# IN-17_tubes_V1_1.net
KiCad netlist of a schematic drawn in EAGLE
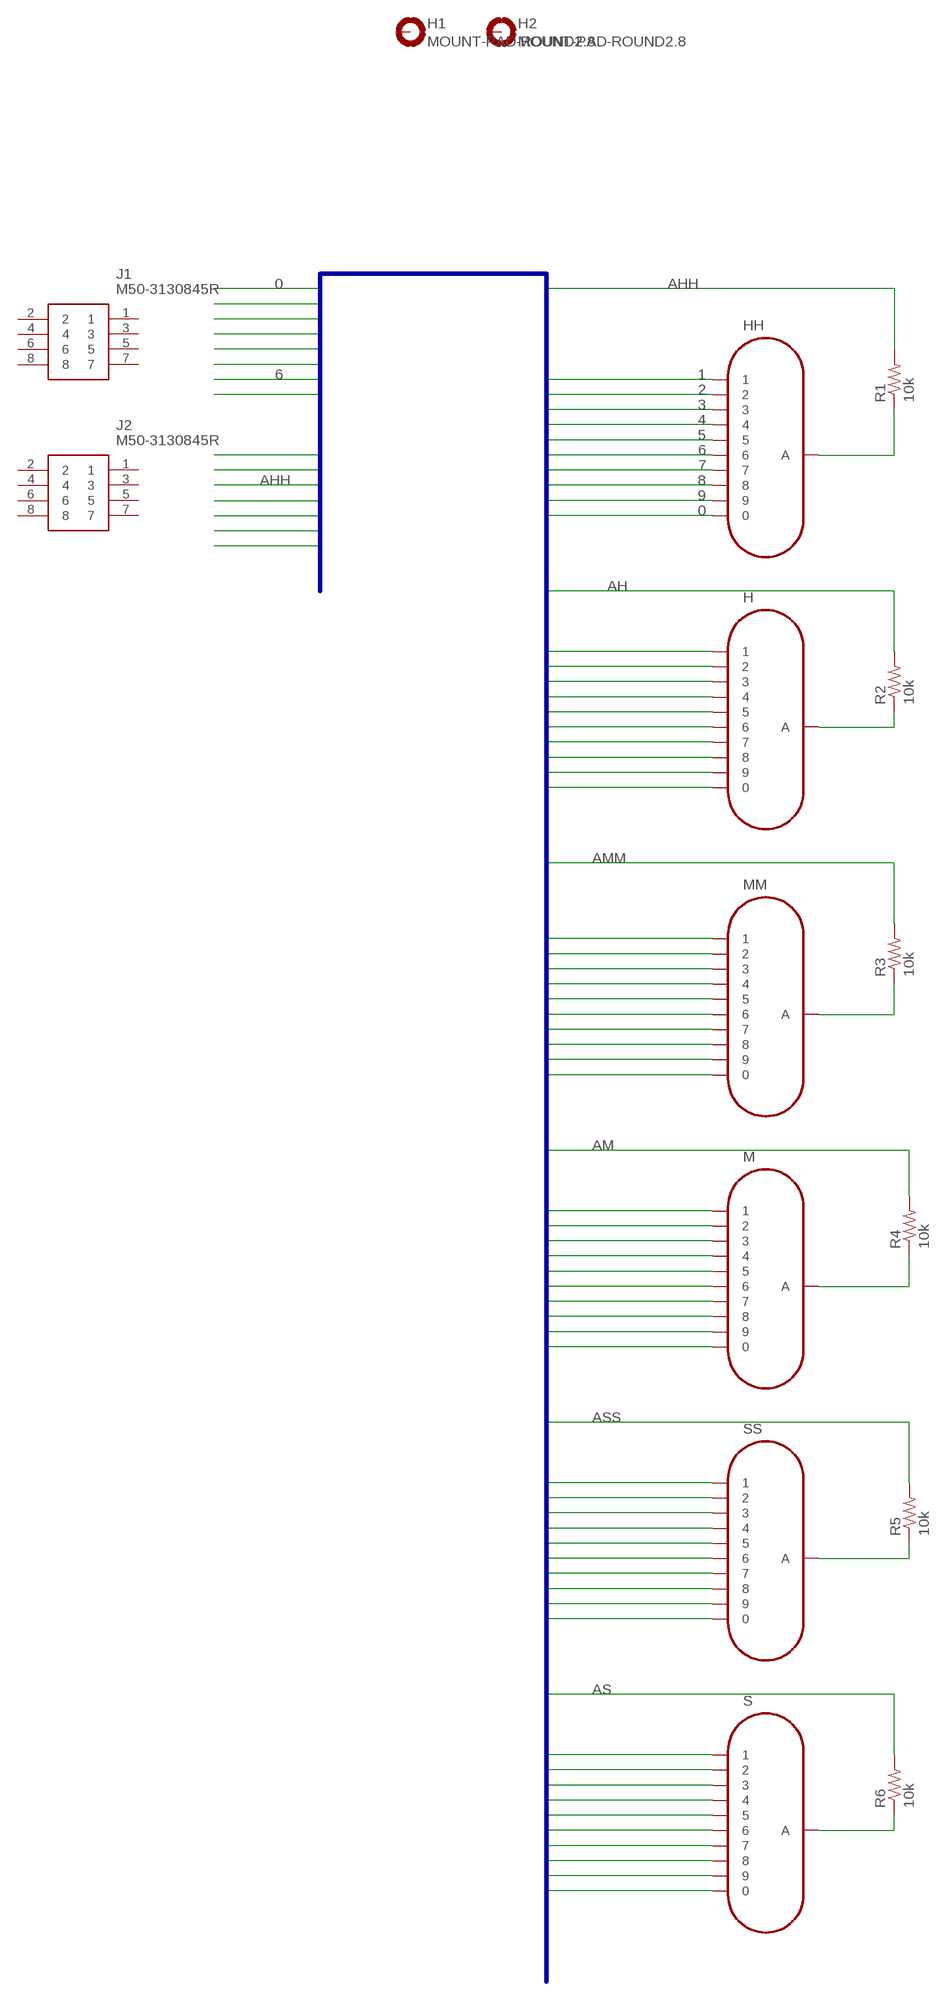
[diagram p0: schematic, sheet 1]

(export (version "E")
  (design (tool "Eeschema 10.0.6"))
  (components
    (comp (ref "H")
      (value "IN-17")
      (footprint "eagle-import:IN-17")
      (libsource (lib "eagle-import") (part "IN-17"))
    )
    (comp (ref "H1")
      (value "MOUNT-PAD-ROUND2.8")
      (footprint "eagle-import:2,8-PAD")
      (libsource (lib "eagle-import") (part "MOUNT-PAD-ROUND2.8"))
    )
    (comp (ref "H2")
      (value "MOUNT-PAD-ROUND2.8")
      (footprint "eagle-import:2,8-PAD")
      (libsource (lib "eagle-import") (part "MOUNT-PAD-ROUND2.8"))
    )
    (comp (ref "HH")
      (value "IN-17")
      (footprint "eagle-import:IN-17")
      (libsource (lib "eagle-import") (part "IN-17"))
    )
    (comp (ref "J1")
      (value "M50-3130845R")
      (footprint "eagle-import:M503130845R")
      (fields (field (name "MOUSER_PART_NUMBER") "855-M50-3130845R"))
      (libsource (lib "eagle-import") (part "M50-3130845R"))
    )
    (comp (ref "J2")
      (value "M50-3130845R")
      (footprint "eagle-import:M503130845R")
      (fields (field (name "MOUSER_PART_NUMBER") "855-M50-3130845R"))
      (libsource (lib "eagle-import") (part "M50-3130845R"))
    )
    (comp (ref "M")
      (value "IN-17")
      (footprint "eagle-import:IN-17")
      (libsource (lib "eagle-import") (part "IN-17"))
    )
    (comp (ref "MM")
      (value "IN-17")
      (footprint "eagle-import:IN-17")
      (libsource (lib "eagle-import") (part "IN-17"))
    )
    (comp (ref "R1")
      (value "10k")
      (footprint "eagle-import:R0805")
      (libsource (lib "eagle-import") (part "R-US_R0805"))
    )
    (comp (ref "R2")
      (value "10k")
      (footprint "eagle-import:R0805")
      (libsource (lib "eagle-import") (part "R-US_R0805"))
    )
    (comp (ref "R3")
      (value "10k")
      (footprint "eagle-import:R0805")
      (libsource (lib "eagle-import") (part "R-US_R0805"))
    )
    (comp (ref "R4")
      (value "10k")
      (footprint "eagle-import:R0805")
      (libsource (lib "eagle-import") (part "R-US_R0805"))
    )
    (comp (ref "R5")
      (value "10k")
      (footprint "eagle-import:R0805")
      (libsource (lib "eagle-import") (part "R-US_R0805"))
    )
    (comp (ref "R6")
      (value "10k")
      (footprint "eagle-import:R0805")
      (libsource (lib "eagle-import") (part "R-US_R0805"))
    )
    (comp (ref "S")
      (value "IN-17")
      (footprint "eagle-import:IN-17")
      (libsource (lib "eagle-import") (part "IN-17"))
    )
    (comp (ref "SS")
      (value "IN-17")
      (footprint "eagle-import:IN-17")
      (libsource (lib "eagle-import") (part "IN-17"))
    )
  )
  (nets
    (net (code "1") (name "/0") (class "Default")
      (node (ref "H") (pin "0") (pinfunction "0_0") (pintype "bidirectional"))
      (node (ref "HH") (pin "0") (pinfunction "0_0") (pintype "bidirectional"))
      (node (ref "M") (pin "0") (pinfunction "0_0") (pintype "bidirectional"))
      (node (ref "MM") (pin "0") (pinfunction "0_0") (pintype "bidirectional"))
      (node (ref "S") (pin "0") (pinfunction "0_0") (pintype "bidirectional"))
      (node (ref "SS") (pin "0") (pinfunction "0_0") (pintype "bidirectional"))
    )
    (net (code "2") (name "/1") (class "Default")
      (node (ref "H") (pin "1") (pinfunction "1_1") (pintype "bidirectional"))
      (node (ref "HH") (pin "1") (pinfunction "1_1") (pintype "bidirectional"))
      (node (ref "M") (pin "1") (pinfunction "1_1") (pintype "bidirectional"))
      (node (ref "MM") (pin "1") (pinfunction "1_1") (pintype "bidirectional"))
      (node (ref "S") (pin "1") (pinfunction "1_1") (pintype "bidirectional"))
      (node (ref "SS") (pin "1") (pinfunction "1_1") (pintype "bidirectional"))
    )
    (net (code "3") (name "/2") (class "Default")
      (node (ref "H") (pin "2") (pinfunction "2_2") (pintype "bidirectional"))
      (node (ref "HH") (pin "2") (pinfunction "2_2") (pintype "bidirectional"))
      (node (ref "M") (pin "2") (pinfunction "2_2") (pintype "bidirectional"))
      (node (ref "MM") (pin "2") (pinfunction "2_2") (pintype "bidirectional"))
      (node (ref "S") (pin "2") (pinfunction "2_2") (pintype "bidirectional"))
      (node (ref "SS") (pin "2") (pinfunction "2_2") (pintype "bidirectional"))
    )
    (net (code "4") (name "/3") (class "Default")
      (node (ref "H") (pin "3") (pinfunction "3_3") (pintype "bidirectional"))
      (node (ref "HH") (pin "3") (pinfunction "3_3") (pintype "bidirectional"))
      (node (ref "M") (pin "3") (pinfunction "3_3") (pintype "bidirectional"))
      (node (ref "MM") (pin "3") (pinfunction "3_3") (pintype "bidirectional"))
      (node (ref "S") (pin "3") (pinfunction "3_3") (pintype "bidirectional"))
      (node (ref "SS") (pin "3") (pinfunction "3_3") (pintype "bidirectional"))
    )
    (net (code "5") (name "/4") (class "Default")
      (node (ref "H") (pin "4") (pinfunction "4_4") (pintype "bidirectional"))
      (node (ref "HH") (pin "4") (pinfunction "4_4") (pintype "bidirectional"))
      (node (ref "M") (pin "4") (pinfunction "4_4") (pintype "bidirectional"))
      (node (ref "MM") (pin "4") (pinfunction "4_4") (pintype "bidirectional"))
      (node (ref "S") (pin "4") (pinfunction "4_4") (pintype "bidirectional"))
      (node (ref "SS") (pin "4") (pinfunction "4_4") (pintype "bidirectional"))
    )
    (net (code "6") (name "/5") (class "Default")
      (node (ref "H") (pin "5") (pinfunction "5_5") (pintype "bidirectional"))
      (node (ref "HH") (pin "5") (pinfunction "5_5") (pintype "bidirectional"))
      (node (ref "M") (pin "5") (pinfunction "5_5") (pintype "bidirectional"))
      (node (ref "MM") (pin "5") (pinfunction "5_5") (pintype "bidirectional"))
      (node (ref "S") (pin "5") (pinfunction "5_5") (pintype "bidirectional"))
      (node (ref "SS") (pin "5") (pinfunction "5_5") (pintype "bidirectional"))
    )
    (net (code "7") (name "/6") (class "Default")
      (node (ref "H") (pin "6") (pinfunction "6_6") (pintype "bidirectional"))
      (node (ref "HH") (pin "6") (pinfunction "6_6") (pintype "bidirectional"))
      (node (ref "M") (pin "6") (pinfunction "6_6") (pintype "bidirectional"))
      (node (ref "MM") (pin "6") (pinfunction "6_6") (pintype "bidirectional"))
      (node (ref "S") (pin "6") (pinfunction "6_6") (pintype "bidirectional"))
      (node (ref "SS") (pin "6") (pinfunction "6_6") (pintype "bidirectional"))
    )
    (net (code "8") (name "/7") (class "Default")
      (node (ref "H") (pin "7") (pinfunction "7_7") (pintype "bidirectional"))
      (node (ref "HH") (pin "7") (pinfunction "7_7") (pintype "bidirectional"))
      (node (ref "M") (pin "7") (pinfunction "7_7") (pintype "bidirectional"))
      (node (ref "MM") (pin "7") (pinfunction "7_7") (pintype "bidirectional"))
      (node (ref "S") (pin "7") (pinfunction "7_7") (pintype "bidirectional"))
      (node (ref "SS") (pin "7") (pinfunction "7_7") (pintype "bidirectional"))
    )
    (net (code "9") (name "/8") (class "Default")
      (node (ref "H") (pin "8") (pinfunction "8_8") (pintype "bidirectional"))
      (node (ref "HH") (pin "8") (pinfunction "8_8") (pintype "bidirectional"))
      (node (ref "M") (pin "8") (pinfunction "8_8") (pintype "bidirectional"))
      (node (ref "MM") (pin "8") (pinfunction "8_8") (pintype "bidirectional"))
      (node (ref "S") (pin "8") (pinfunction "8_8") (pintype "bidirectional"))
      (node (ref "SS") (pin "8") (pinfunction "8_8") (pintype "bidirectional"))
    )
    (net (code "10") (name "/9") (class "Default")
      (node (ref "H") (pin "9") (pinfunction "9_9") (pintype "bidirectional"))
      (node (ref "HH") (pin "9") (pinfunction "9_9") (pintype "bidirectional"))
      (node (ref "M") (pin "9") (pinfunction "9_9") (pintype "bidirectional"))
      (node (ref "MM") (pin "9") (pinfunction "9_9") (pintype "bidirectional"))
      (node (ref "S") (pin "9") (pinfunction "9_9") (pintype "bidirectional"))
      (node (ref "SS") (pin "9") (pinfunction "9_9") (pintype "bidirectional"))
    )
    (net (code "11") (name "/AH") (class "Default")
      (node (ref "R2") (pin "2") (pinfunction "2_2") (pintype "passive"))
    )
    (net (code "12") (name "/AHH") (class "Default")
      (node (ref "R1") (pin "2") (pinfunction "2_2") (pintype "passive"))
    )
    (net (code "13") (name "/AM") (class "Default")
      (node (ref "R4") (pin "2") (pinfunction "2_2") (pintype "passive"))
    )
    (net (code "14") (name "/AMM") (class "Default")
      (node (ref "R3") (pin "2") (pinfunction "2_2") (pintype "passive"))
    )
    (net (code "15") (name "/AS") (class "Default")
      (node (ref "R6") (pin "2") (pinfunction "2_2") (pintype "passive"))
    )
    (net (code "16") (name "/ASS") (class "Default")
      (node (ref "R5") (pin "2") (pinfunction "2_2") (pintype "passive"))
    )
    (net (code "17") (name "Net-(H-PadA)") (class "Default")
      (node (ref "H") (pin "A") (pinfunction "A_A") (pintype "bidirectional"))
      (node (ref "R2") (pin "1") (pinfunction "1_1") (pintype "passive"))
    )
    (net (code "18") (name "Net-(HH-PadA)") (class "Default")
      (node (ref "HH") (pin "A") (pinfunction "A_A") (pintype "bidirectional"))
      (node (ref "R1") (pin "1") (pinfunction "1_1") (pintype "passive"))
    )
    (net (code "19") (name "Net-(M-PadA)") (class "Default")
      (node (ref "M") (pin "A") (pinfunction "A_A") (pintype "bidirectional"))
      (node (ref "R4") (pin "1") (pinfunction "1_1") (pintype "passive"))
    )
    (net (code "20") (name "Net-(MM-PadA)") (class "Default")
      (node (ref "MM") (pin "A") (pinfunction "A_A") (pintype "bidirectional"))
      (node (ref "R3") (pin "1") (pinfunction "1_1") (pintype "passive"))
    )
    (net (code "21") (name "Net-(R5-Pad1)") (class "Default")
      (node (ref "R5") (pin "1") (pinfunction "1_1") (pintype "passive"))
      (node (ref "SS") (pin "A") (pinfunction "A_A") (pintype "bidirectional"))
    )
    (net (code "22") (name "Net-(R6-Pad1)") (class "Default")
      (node (ref "R6") (pin "1") (pinfunction "1_1") (pintype "passive"))
      (node (ref "S") (pin "A") (pinfunction "A_A") (pintype "bidirectional"))
    )
    (net (code "23") (name "unconnected-(H1-MOUNT-PadB2,8)") (class "Default")
      (node (ref "H1") (pin "B2,8") (pinfunction "MOUNT_B2,8") (pintype "passive"))
    )
    (net (code "24") (name "unconnected-(H2-MOUNT-PadB2,8)") (class "Default")
      (node (ref "H2") (pin "B2,8") (pinfunction "MOUNT_B2,8") (pintype "passive"))
    )
    (net (code "25") (name "unconnected-(J1-Pad1)") (class "Default")
      (node (ref "J1") (pin "1") (pinfunction "1_1") (pintype "bidirectional"))
    )
    (net (code "26") (name "unconnected-(J1-Pad2)") (class "Default")
      (node (ref "J1") (pin "2") (pinfunction "2_2") (pintype "bidirectional"))
    )
    (net (code "27") (name "unconnected-(J1-Pad3)") (class "Default")
      (node (ref "J1") (pin "3") (pinfunction "3_3") (pintype "bidirectional"))
    )
    (net (code "28") (name "unconnected-(J1-Pad4)") (class "Default")
      (node (ref "J1") (pin "4") (pinfunction "4_4") (pintype "bidirectional"))
    )
    (net (code "29") (name "unconnected-(J1-Pad5)") (class "Default")
      (node (ref "J1") (pin "5") (pinfunction "5_5") (pintype "bidirectional"))
    )
    (net (code "30") (name "unconnected-(J1-Pad6)") (class "Default")
      (node (ref "J1") (pin "6") (pinfunction "6_6") (pintype "bidirectional"))
    )
    (net (code "31") (name "unconnected-(J1-Pad7)") (class "Default")
      (node (ref "J1") (pin "7") (pinfunction "7_7") (pintype "bidirectional"))
    )
    (net (code "32") (name "unconnected-(J1-Pad8)") (class "Default")
      (node (ref "J1") (pin "8") (pinfunction "8_8") (pintype "bidirectional"))
    )
    (net (code "33") (name "unconnected-(J2-Pad1)") (class "Default")
      (node (ref "J2") (pin "1") (pinfunction "1_1") (pintype "bidirectional"))
    )
    (net (code "34") (name "unconnected-(J2-Pad2)") (class "Default")
      (node (ref "J2") (pin "2") (pinfunction "2_2") (pintype "bidirectional"))
    )
    (net (code "35") (name "unconnected-(J2-Pad3)") (class "Default")
      (node (ref "J2") (pin "3") (pinfunction "3_3") (pintype "bidirectional"))
    )
    (net (code "36") (name "unconnected-(J2-Pad4)") (class "Default")
      (node (ref "J2") (pin "4") (pinfunction "4_4") (pintype "bidirectional"))
    )
    (net (code "37") (name "unconnected-(J2-Pad5)") (class "Default")
      (node (ref "J2") (pin "5") (pinfunction "5_5") (pintype "bidirectional"))
    )
    (net (code "38") (name "unconnected-(J2-Pad6)") (class "Default")
      (node (ref "J2") (pin "6") (pinfunction "6_6") (pintype "bidirectional"))
    )
    (net (code "39") (name "unconnected-(J2-Pad7)") (class "Default")
      (node (ref "J2") (pin "7") (pinfunction "7_7") (pintype "bidirectional"))
    )
    (net (code "40") (name "unconnected-(J2-Pad8)") (class "Default")
      (node (ref "J2") (pin "8") (pinfunction "8_8") (pintype "bidirectional"))
    )
  )
)
